# usb_hub.net
KiCad netlist of a schematic drawn in Altium Designer
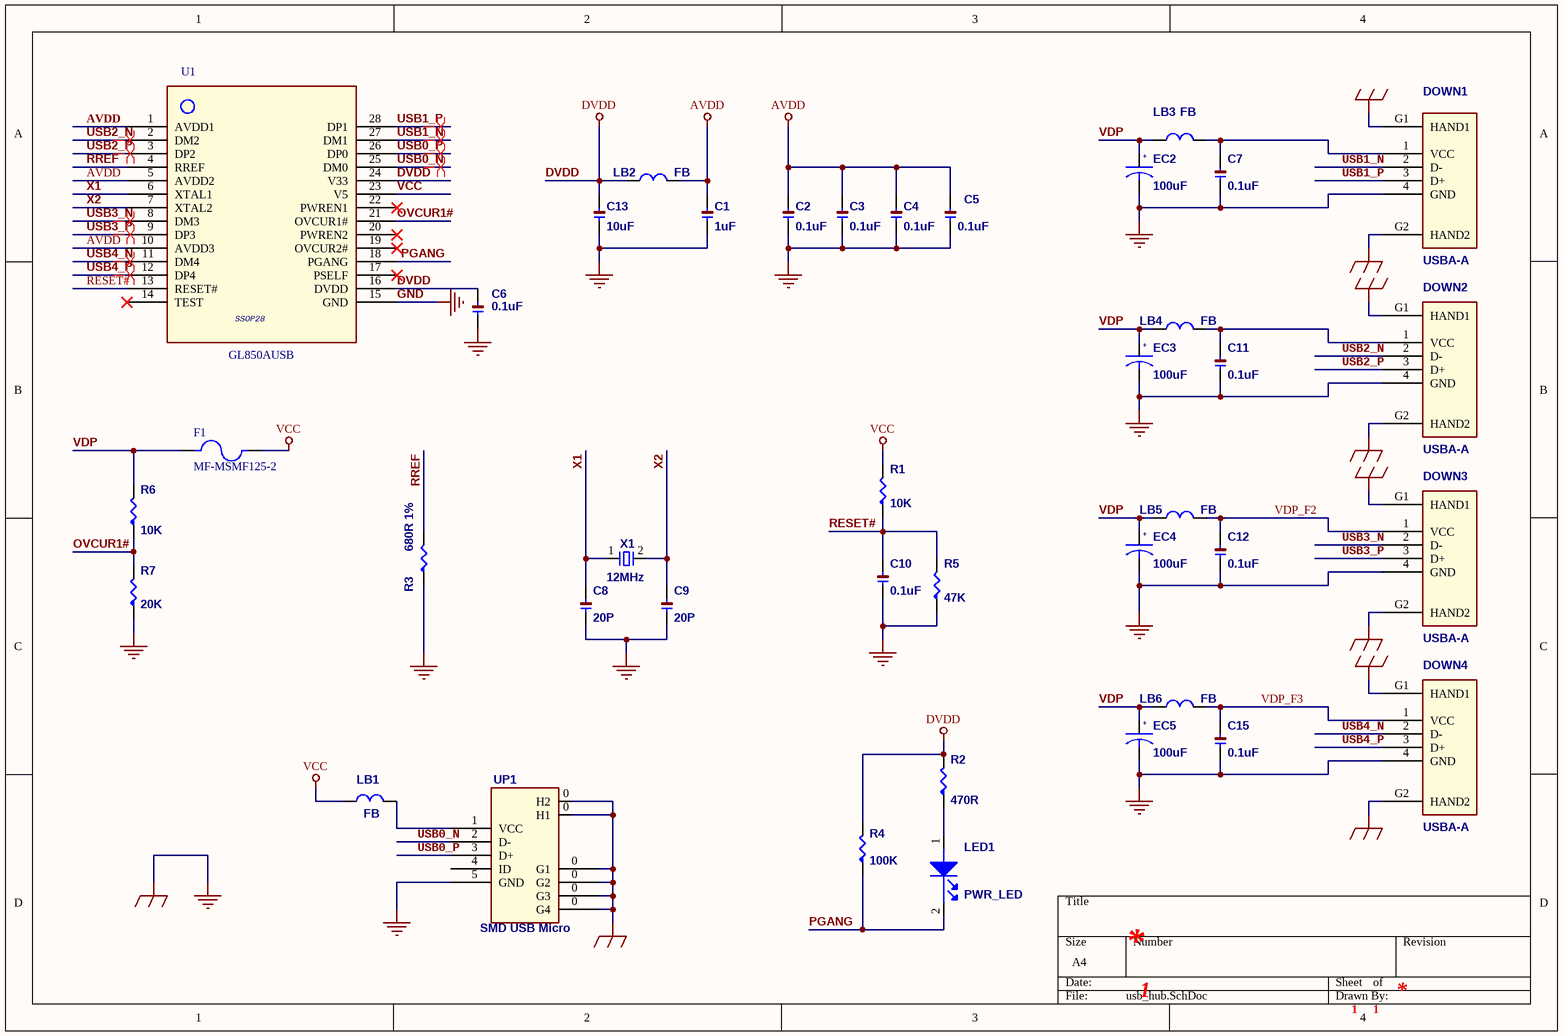
[diagram p0: usb_hub.SchDoc]

(export (version "E")
  (design (tool "Eeschema 10.0.6"))
  (components
    (comp (ref "C1") (value "1uF") (footprint "C0603") (libsource (lib "*") (part "C-0603")))
    (comp (ref "C2") (value "0.1uF") (footprint "C0603") (libsource (lib "*") (part "C-0603")))
    (comp (ref "C3") (value "0.1uF") (footprint "C0603") (libsource (lib "*") (part "C-0603")))
    (comp (ref "C4") (value "0.1uF") (footprint "C0603") (libsource (lib "*") (part "C-0603")))
    (comp (ref "C5") (value "0.1uF") (footprint "C0603") (libsource (lib "*") (part "C-0603")))
    (comp (ref "C6") (value "0.1uF") (footprint "C0603") (libsource (lib "*") (part "C-0603")))
    (comp (ref "C7") (value "0.1uF") (footprint "C0603") (libsource (lib "*") (part "C-0603")))
    (comp (ref "C8") (value "20P") (footprint "C0603") (libsource (lib "*") (part "C-0603")))
    (comp (ref "C9") (value "20P") (footprint "C0603") (libsource (lib "*") (part "C-0603")))
    (comp (ref "C10") (value "0.1uF") (footprint "C0603") (libsource (lib "*") (part "C-0603")))
    (comp (ref "C11") (value "0.1uF") (footprint "C0603") (libsource (lib "*") (part "C-0603")))
    (comp (ref "C12") (value "0.1uF") (footprint "C0603") (libsource (lib "*") (part "C-0603")))
    (comp (ref "C13") (value "10uF") (footprint "C0603") (libsource (lib "*") (part "C-0603")))
    (comp (ref "C15") (value "0.1uF") (footprint "C0603") (libsource (lib "*") (part "C-0603")))
    (comp (ref "DOWN1") (value "USBA-A") (footprint "USBA-A") (libsource (lib "*") (part "USBA-A")))
    (comp (ref "DOWN2") (value "USBA-A") (footprint "USBA-A") (libsource (lib "*") (part "USBA-A")))
    (comp (ref "DOWN3") (value "USBA-A") (footprint "USBA-A") (libsource (lib "*") (part "USBA-A")))
    (comp (ref "DOWN4") (value "USBA-A") (footprint "USBA-A") (libsource (lib "*") (part "USBA-A")))
    (comp (ref "EC2") (value "100uF") (footprint "CED-6_3-2_5") (libsource (lib "*") (part "CE-100UF/16V")))
    (comp (ref "EC3") (value "100uF") (footprint "CED-6_3-2_5") (libsource (lib "*") (part "CE-100UF/16V")))
    (comp (ref "EC4") (value "100uF") (footprint "CED-6_3-2_5") (libsource (lib "*") (part "CE-100UF/16V")))
    (comp (ref "EC5") (value "100uF") (footprint "CED-6_3-2_5") (libsource (lib "*") (part "CE-100UF/16V")))
    (comp (ref "F1")
      (value "MF-MSMF125-2")
      (footprint "FUSER_MF-MSMF125-2")
      (description "Polymeric PTC Resettable Fuse 6V 1.25 A Ih Surface Mount 1812 (4532 Metric), Concave")
      (fields (field (name "MF") "Bourns"))
      (libsource (lib "MF-MSMF125-2") (part "MF-MSMF125-2"))
    )
    (comp (ref "LB1") (value "FB") (footprint "L0805") (libsource (lib "") (part "FB-0805_1")))
    (comp (ref "LB2") (value "FB") (footprint "L0805") (libsource (lib "*") (part "FB-0805")))
    (comp (ref "LB3") (value "FB") (footprint "L0805") (libsource (lib "") (part "FB-0805_1")))
    (comp (ref "LB4") (value "FB") (footprint "L0805") (libsource (lib "*") (part "FB-0805")))
    (comp (ref "LB5") (value "FB") (footprint "L0805") (libsource (lib "*") (part "FB-0805")))
    (comp (ref "LB6") (value "FB") (footprint "L0805") (libsource (lib "*") (part "FB-0805")))
    (comp (ref "LED1") (value "PWR_LED") (footprint "LED0805") (libsource (lib "*") (part "LED-3mm_0")))
    (comp (ref "R1") (value "10K") (footprint "R0603") (libsource (lib "*") (part "R-0603")))
    (comp (ref "R2") (value "470R") (footprint "R0603") (libsource (lib "*") (part "R-0603")))
    (comp (ref "R3") (value "680R 1%") (footprint "R0603") (libsource (lib "*") (part "R-0603 1%")))
    (comp (ref "R4") (value "100K") (footprint "R0603") (libsource (lib "*") (part "R-0603")))
    (comp (ref "R5") (value "47K") (footprint "R0603") (libsource (lib "*") (part "R-0603")))
    (comp (ref "R6") (value "10K") (footprint "R0603") (libsource (lib "*") (part "R-0603")))
    (comp (ref "R7") (value "20K") (footprint "R0603") (libsource (lib "*") (part "R-0603")))
    (comp (ref "U1") (value "GL850AUSB") (footprint "SSOP28") (libsource (lib "*") (part "GLI8024-48_3")))
    (comp (ref "UP1")
      (value "SMD USB Micro")
      (footprint "Micro_USB_MK5P")
      (libsource (lib "*") (part "CNS-USBminiAB-A"))
    )
    (comp (ref "X1") (value "12MHz") (footprint "XTAL-49SMA-H4.2") (libsource (lib "*") (part "XD-49US-A")))
  )
  (nets
    (net (code "1") (name "/OVCUR1#") (class "Default")
      (node (ref "R6") (pin "1") (pinfunction "1_1") (pintype "passive"))
      (node (ref "R7") (pin "2") (pinfunction "2_2") (pintype "passive"))
      (node (ref "U1") (pin "21") (pinfunction "OVCUR1#_21") (pintype "passive"))
    )
    (net (code "2") (name "/PGANG") (class "Default")
      (node (ref "LED1") (pin "2") (pinfunction "2_2") (pintype "passive"))
      (node (ref "R4") (pin "1") (pinfunction "1_1") (pintype "passive"))
      (node (ref "U1") (pin "18") (pinfunction "PGANG_18") (pintype "passive"))
    )
    (net (code "3") (name "/RESET#") (class "Default")
      (node (ref "C10") (pin "2") (pinfunction "2_2") (pintype "passive"))
      (node (ref "R1") (pin "1") (pinfunction "1_1") (pintype "passive"))
      (node (ref "R5") (pin "2") (pinfunction "2_2") (pintype "passive"))
      (node (ref "U1") (pin "13") (pinfunction "RESET#_13") (pintype "passive"))
    )
    (net (code "4") (name "/RREF") (class "Default")
      (node (ref "R3") (pin "2") (pinfunction "2_2") (pintype "passive"))
      (node (ref "U1") (pin "4") (pinfunction "RREF_4") (pintype "passive"))
    )
    (net (code "5") (name "/USB0_N") (class "Default")
      (node (ref "U1") (pin "25") (pinfunction "DM0_25") (pintype "passive"))
      (node (ref "UP1") (pin "2") (pinfunction "D-_2") (pintype "passive"))
    )
    (net (code "6") (name "/USB0_P") (class "Default")
      (node (ref "U1") (pin "26") (pinfunction "DP0_26") (pintype "passive"))
      (node (ref "UP1") (pin "3") (pinfunction "D+_3") (pintype "passive"))
    )
    (net (code "7") (name "/USB1_N") (class "Default")
      (node (ref "DOWN1") (pin "2") (pinfunction "D-_2") (pintype "passive"))
      (node (ref "U1") (pin "27") (pinfunction "DM1_27") (pintype "passive"))
    )
    (net (code "8") (name "/USB1_P") (class "Default")
      (node (ref "DOWN1") (pin "3") (pinfunction "D+_3") (pintype "passive"))
      (node (ref "U1") (pin "28") (pinfunction "DP1_28") (pintype "passive"))
    )
    (net (code "9") (name "/USB2_N") (class "Default")
      (node (ref "DOWN2") (pin "2") (pinfunction "D-_2") (pintype "passive"))
      (node (ref "U1") (pin "2") (pinfunction "DM2_2") (pintype "passive"))
    )
    (net (code "10") (name "/USB2_P") (class "Default")
      (node (ref "DOWN2") (pin "3") (pinfunction "D+_3") (pintype "passive"))
      (node (ref "U1") (pin "3") (pinfunction "DP2_3") (pintype "passive"))
    )
    (net (code "11") (name "/USB3_N") (class "Default")
      (node (ref "DOWN3") (pin "2") (pinfunction "D-_2") (pintype "passive"))
      (node (ref "U1") (pin "8") (pinfunction "DM3_8") (pintype "passive"))
    )
    (net (code "12") (name "/USB3_P") (class "Default")
      (node (ref "DOWN3") (pin "3") (pinfunction "D+_3") (pintype "passive"))
      (node (ref "U1") (pin "9") (pinfunction "DP3_9") (pintype "passive"))
    )
    (net (code "13") (name "/USB4_N") (class "Default")
      (node (ref "DOWN4") (pin "2") (pinfunction "D-_2") (pintype "passive"))
      (node (ref "U1") (pin "11") (pinfunction "DM4_11") (pintype "passive"))
    )
    (net (code "14") (name "/USB4_P") (class "Default")
      (node (ref "DOWN4") (pin "3") (pinfunction "D+_3") (pintype "passive"))
      (node (ref "U1") (pin "12") (pinfunction "DP4_12") (pintype "passive"))
    )
    (net (code "15") (name "/VDP") (class "Default")
      (node (ref "EC2") (pin "1") (pinfunction "1_1") (pintype "passive"))
      (node (ref "EC3") (pin "1") (pinfunction "1_1") (pintype "passive"))
      (node (ref "EC4") (pin "1") (pinfunction "1_1") (pintype "passive"))
      (node (ref "EC5") (pin "1") (pinfunction "1_1") (pintype "passive"))
      (node (ref "F1") (pin "1") (pinfunction "1_1") (pintype "passive"))
      (node (ref "LB3") (pin "1") (pinfunction "1_1") (pintype "passive"))
      (node (ref "LB4") (pin "2") (pinfunction "2_2") (pintype "passive"))
      (node (ref "LB5") (pin "2") (pinfunction "2_2") (pintype "passive"))
      (node (ref "LB6") (pin "2") (pinfunction "2_2") (pintype "passive"))
      (node (ref "R6") (pin "2") (pinfunction "2_2") (pintype "passive"))
    )
    (net (code "16") (name "/VDP_F2") (class "Default")
      (node (ref "C12") (pin "2") (pinfunction "2_2") (pintype "passive"))
      (node (ref "DOWN3") (pin "1") (pinfunction "VCC_1") (pintype "passive"))
      (node (ref "LB5") (pin "1") (pinfunction "1_1") (pintype "passive"))
    )
    (net (code "17") (name "/VDP_F3") (class "Default")
      (node (ref "C15") (pin "2") (pinfunction "2_2") (pintype "passive"))
      (node (ref "DOWN4") (pin "1") (pinfunction "VCC_1") (pintype "passive"))
      (node (ref "LB6") (pin "1") (pinfunction "1_1") (pintype "passive"))
    )
    (net (code "18") (name "/X1") (class "Default")
      (node (ref "C8") (pin "2") (pinfunction "2_2") (pintype "passive"))
      (node (ref "U1") (pin "6") (pinfunction "XTAL1_6") (pintype "passive"))
      (node (ref "X1") (pin "1") (pinfunction "1_1") (pintype "passive"))
    )
    (net (code "19") (name "/X2") (class "Default")
      (node (ref "C9") (pin "2") (pinfunction "2_2") (pintype "passive"))
      (node (ref "U1") (pin "7") (pinfunction "XTAL2_7") (pintype "passive"))
      (node (ref "X1") (pin "2") (pinfunction "2_2") (pintype "passive"))
    )
    (net (code "20") (name "AVDD") (class "Default")
      (node (ref "C1") (pin "2") (pinfunction "2_2") (pintype "passive"))
      (node (ref "C2") (pin "2") (pinfunction "2_2") (pintype "passive"))
      (node (ref "C3") (pin "2") (pinfunction "2_2") (pintype "passive"))
      (node (ref "C4") (pin "2") (pinfunction "2_2") (pintype "passive"))
      (node (ref "C5") (pin "2") (pinfunction "2_2") (pintype "passive"))
      (node (ref "LB2") (pin "1") (pinfunction "1_1") (pintype "passive"))
      (node (ref "U1") (pin "1") (pinfunction "AVDD1_1") (pintype "passive"))
      (node (ref "U1") (pin "10") (pinfunction "AVDD3_10") (pintype "passive"))
      (node (ref "U1") (pin "5") (pinfunction "AVDD2_5") (pintype "passive"))
    )
    (net (code "21") (name "DVDD") (class "Default")
      (node (ref "C13") (pin "2") (pinfunction "2_2") (pintype "passive"))
      (node (ref "C6") (pin "2") (pinfunction "2_2") (pintype "passive"))
      (node (ref "LB2") (pin "2") (pinfunction "2_2") (pintype "passive"))
      (node (ref "R2") (pin "2") (pinfunction "2_2") (pintype "passive"))
      (node (ref "R4") (pin "2") (pinfunction "2_2") (pintype "passive"))
      (node (ref "U1") (pin "16") (pinfunction "DVDD_16") (pintype "passive"))
      (node (ref "U1") (pin "24") (pinfunction "V33_24") (pintype "passive"))
    )
    (net (code "22") (name "GND") (class "Default")
      (node (ref "C1") (pin "1") (pinfunction "1_1") (pintype "passive"))
      (node (ref "C10") (pin "1") (pinfunction "1_1") (pintype "passive"))
      (node (ref "C11") (pin "1") (pinfunction "1_1") (pintype "passive"))
      (node (ref "C12") (pin "1") (pinfunction "1_1") (pintype "passive"))
      (node (ref "C13") (pin "1") (pinfunction "1_1") (pintype "passive"))
      (node (ref "C15") (pin "1") (pinfunction "1_1") (pintype "passive"))
      (node (ref "C2") (pin "1") (pinfunction "1_1") (pintype "passive"))
      (node (ref "C3") (pin "1") (pinfunction "1_1") (pintype "passive"))
      (node (ref "C4") (pin "1") (pinfunction "1_1") (pintype "passive"))
      (node (ref "C5") (pin "1") (pinfunction "1_1") (pintype "passive"))
      (node (ref "C6") (pin "1") (pinfunction "1_1") (pintype "passive"))
      (node (ref "C7") (pin "1") (pinfunction "1_1") (pintype "passive"))
      (node (ref "C8") (pin "1") (pinfunction "1_1") (pintype "passive"))
      (node (ref "C9") (pin "1") (pinfunction "1_1") (pintype "passive"))
      (node (ref "DOWN1") (pin "4") (pinfunction "GND_4") (pintype "passive"))
      (node (ref "DOWN1") (pin "G1") (pinfunction "HAND1_G1") (pintype "passive"))
      (node (ref "DOWN1") (pin "G2") (pinfunction "HAND2_G2") (pintype "passive"))
      (node (ref "DOWN2") (pin "4") (pinfunction "GND_4") (pintype "passive"))
      (node (ref "DOWN2") (pin "G1") (pinfunction "HAND1_G1") (pintype "passive"))
      (node (ref "DOWN2") (pin "G2") (pinfunction "HAND2_G2") (pintype "passive"))
      (node (ref "DOWN3") (pin "4") (pinfunction "GND_4") (pintype "passive"))
      (node (ref "DOWN3") (pin "G1") (pinfunction "HAND1_G1") (pintype "passive"))
      (node (ref "DOWN3") (pin "G2") (pinfunction "HAND2_G2") (pintype "passive"))
      (node (ref "DOWN4") (pin "4") (pinfunction "GND_4") (pintype "passive"))
      (node (ref "DOWN4") (pin "G1") (pinfunction "HAND1_G1") (pintype "passive"))
      (node (ref "DOWN4") (pin "G2") (pinfunction "HAND2_G2") (pintype "passive"))
      (node (ref "EC2") (pin "2") (pinfunction "2_2") (pintype "passive"))
      (node (ref "EC3") (pin "2") (pinfunction "2_2") (pintype "passive"))
      (node (ref "EC4") (pin "2") (pinfunction "2_2") (pintype "passive"))
      (node (ref "EC5") (pin "2") (pinfunction "2_2") (pintype "passive"))
      (node (ref "R3") (pin "1") (pinfunction "1_1") (pintype "passive"))
      (node (ref "R5") (pin "1") (pinfunction "1_1") (pintype "passive"))
      (node (ref "R7") (pin "1") (pinfunction "1_1") (pintype "passive"))
      (node (ref "U1") (pin "15") (pinfunction "GND_15") (pintype "passive"))
      (node (ref "UP1") (pin "0") (pinfunction "H1_0") (pintype "passive"))
      (node (ref "UP1") (pin "5") (pinfunction "GND_5") (pintype "passive"))
    )
    (net (code "23") (name "Net-(DOWN1-VCC)") (class "Default")
      (node (ref "C7") (pin "2") (pinfunction "2_2") (pintype "passive"))
      (node (ref "DOWN1") (pin "1") (pinfunction "VCC_1") (pintype "passive"))
      (node (ref "LB3") (pin "2") (pinfunction "2_2") (pintype "passive"))
    )
    (net (code "24") (name "Net-(DOWN2-VCC)") (class "Default")
      (node (ref "C11") (pin "2") (pinfunction "2_2") (pintype "passive"))
      (node (ref "DOWN2") (pin "1") (pinfunction "VCC_1") (pintype "passive"))
      (node (ref "LB4") (pin "1") (pinfunction "1_1") (pintype "passive"))
    )
    (net (code "25") (name "Net-(LED1-Pad1)") (class "Default")
      (node (ref "LED1") (pin "1") (pinfunction "1_1") (pintype "passive"))
      (node (ref "R2") (pin "1") (pinfunction "1_1") (pintype "passive"))
    )
    (net (code "26") (name "Net-(UP1-VCC)") (class "Default")
      (node (ref "LB1") (pin "2") (pinfunction "2_2") (pintype "passive"))
      (node (ref "UP1") (pin "1") (pinfunction "VCC_1") (pintype "passive"))
    )
    (net (code "27") (name "VCC") (class "Default")
      (node (ref "F1") (pin "2") (pinfunction "2_2") (pintype "passive"))
      (node (ref "LB1") (pin "1") (pinfunction "1_1") (pintype "passive"))
      (node (ref "R1") (pin "2") (pinfunction "2_2") (pintype "passive"))
      (node (ref "U1") (pin "23") (pinfunction "V5_23") (pintype "passive"))
    )
    (net (code "28") (name "unconnected-(U1-OVCUR2#-Pad19)") (class "Default")
      (node (ref "U1") (pin "19") (pinfunction "OVCUR2#_19") (pintype "passive+no_connect"))
    )
    (net (code "29") (name "unconnected-(U1-PSELF-Pad17)") (class "Default")
      (node (ref "U1") (pin "17") (pinfunction "PSELF_17") (pintype "passive+no_connect"))
    )
    (net (code "30") (name "unconnected-(U1-PWREN1-Pad22)") (class "Default")
      (node (ref "U1") (pin "22") (pinfunction "PWREN1_22") (pintype "passive+no_connect"))
    )
    (net (code "31") (name "unconnected-(U1-PWREN2-Pad20)") (class "Default")
      (node (ref "U1") (pin "20") (pinfunction "PWREN2_20") (pintype "passive+no_connect"))
    )
    (net (code "32") (name "unconnected-(U1-TEST-Pad14)") (class "Default")
      (node (ref "U1") (pin "14") (pinfunction "TEST_14") (pintype "passive+no_connect"))
    )
    (net (code "33") (name "unconnected-(UP1-ID-Pad4)") (class "Default")
      (node (ref "UP1") (pin "4") (pinfunction "ID_4") (pintype "passive"))
    )
  )
)
